# Adafruit_DAC7578P_Breakout.net
KiCad netlist of a schematic drawn in EAGLE
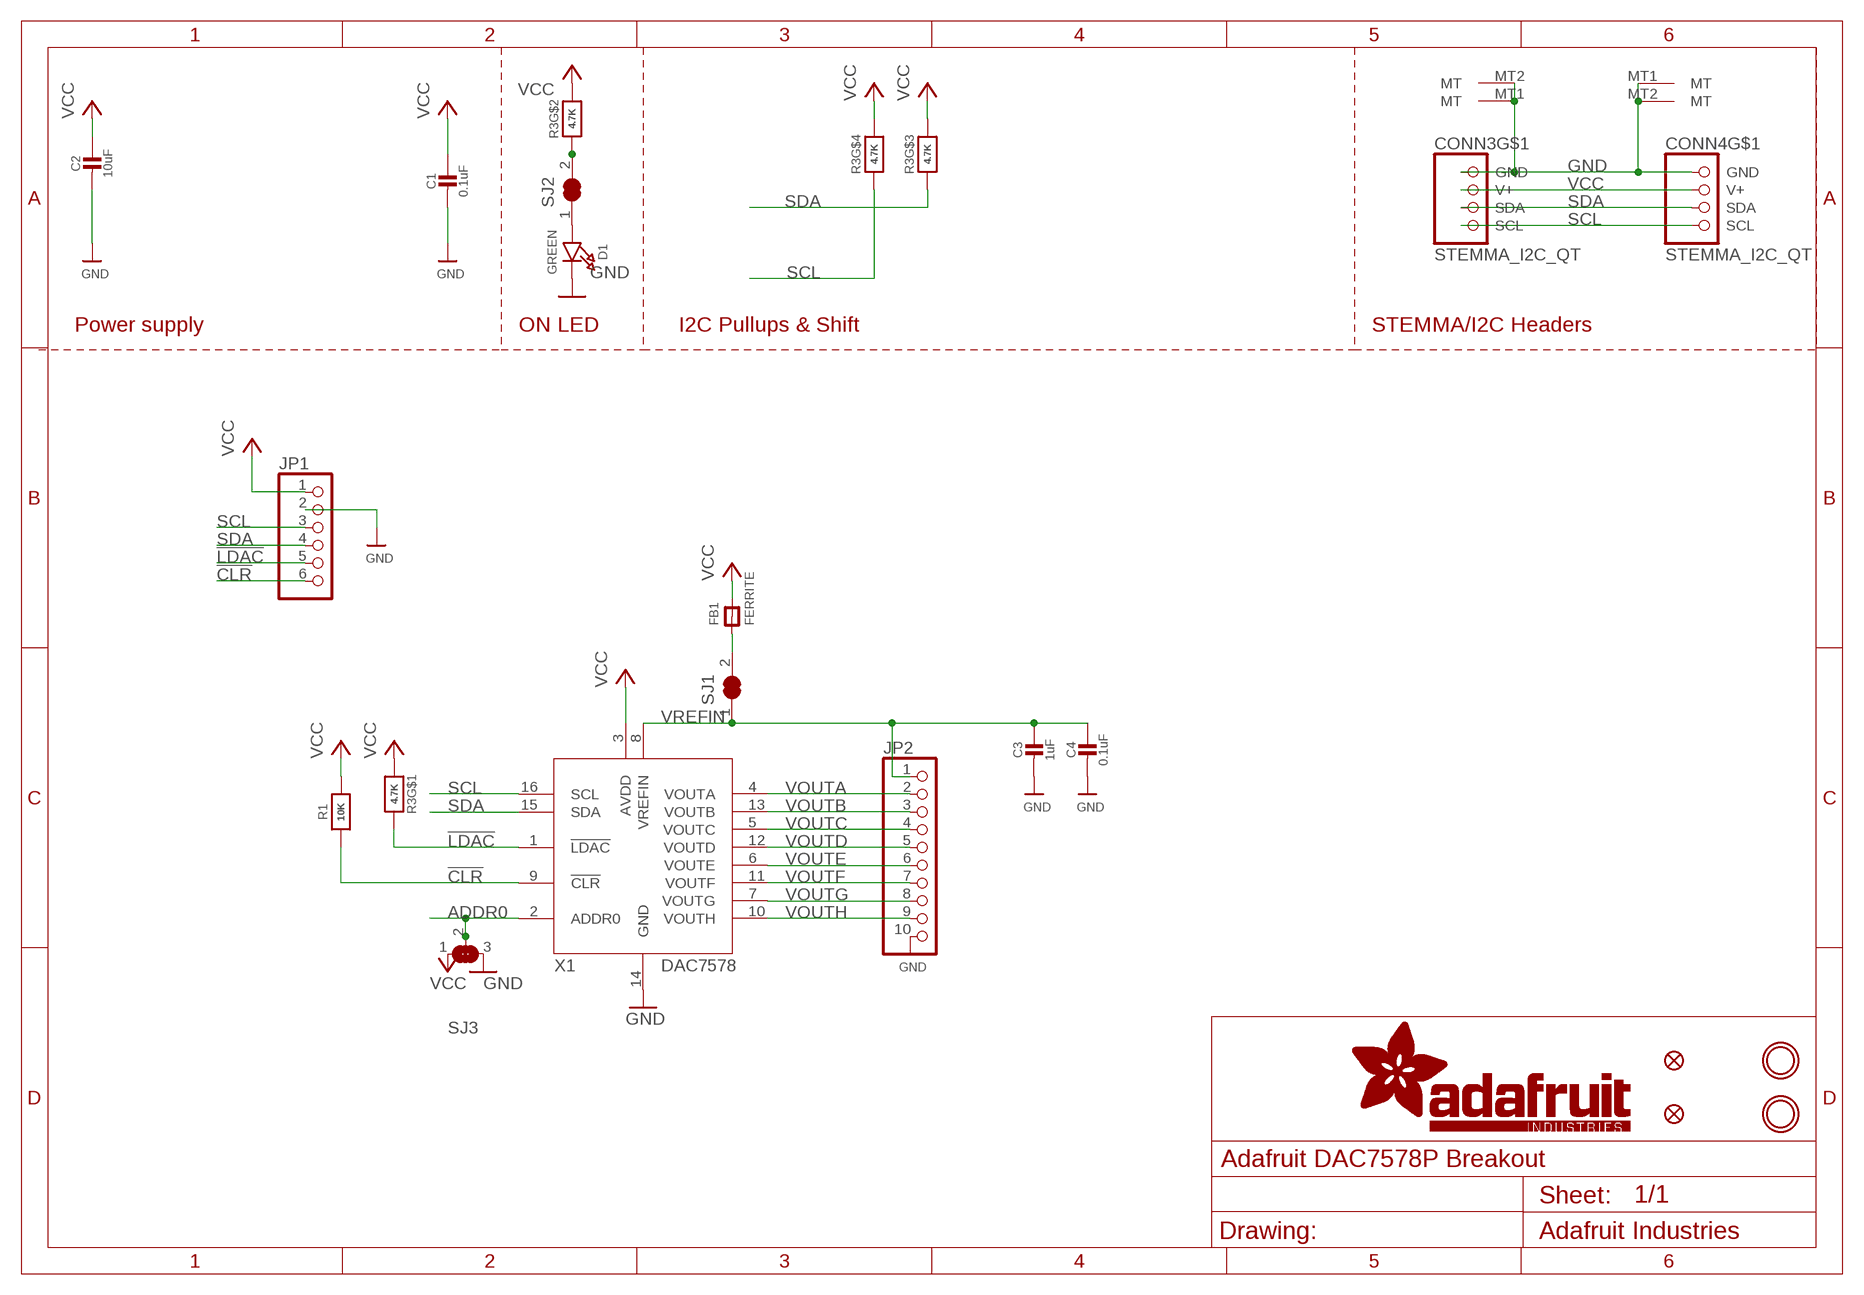
[diagram p0: schematic, sheet 1]

(export (version "E")
  (design (tool "Eeschema 10.0.6"))
  (components
    (comp (ref "C1")
      (value "0.1uF")
      (footprint "eagle-import:0603-NO")
      (libsource (lib "eagle-import") (part "CAP_CERAMIC0603_NO"))
    )
    (comp (ref "C2")
      (value "10uF")
      (footprint "eagle-import:0805-NO")
      (libsource (lib "eagle-import") (part "CAP_CERAMIC0805-NOOUTLINE"))
    )
    (comp (ref "C3")
      (value "1uF")
      (footprint "eagle-import:0603-NO")
      (libsource (lib "eagle-import") (part "CAP_CERAMIC0603_NO"))
    )
    (comp (ref "C4")
      (value "0.1uF")
      (footprint "eagle-import:0603-NO")
      (libsource (lib "eagle-import") (part "CAP_CERAMIC0603_NO"))
    )
    (comp (ref "CONN3")
      (value "STEMMA_I2C_QT")
      (footprint "eagle-import:JST_SH4")
      (libsource (lib "eagle-import") (part "STEMMA_I2C_QT"))
    )
    (comp (ref "CONN4")
      (value "STEMMA_I2C_QT")
      (footprint "eagle-import:JST_SH4")
      (libsource (lib "eagle-import") (part "STEMMA_I2C_QT"))
    )
    (comp (ref "D1")
      (value "GREEN")
      (footprint "eagle-import:CHIPLED_0603_NOOUTLINE")
      (libsource (lib "eagle-import") (part "LED0603_NOOUTLINE"))
    )
    (comp (ref "FB1")
      (value "FERRITE")
      (footprint "eagle-import:0603-NO")
      (libsource (lib "eagle-import") (part "FERRITE-0603NO"))
    )
    (comp (ref "FID3")
      (value "FIDUCIAL_0.5MM")
      (footprint "eagle-import:FIDUCIAL_0.5MM")
      (libsource (lib "eagle-import") (part "FIDUCIAL_0.5MM"))
    )
    (comp (ref "FID4")
      (value "FIDUCIAL_0.5MM")
      (footprint "eagle-import:FIDUCIAL_0.5MM")
      (libsource (lib "eagle-import") (part "FIDUCIAL_0.5MM"))
    )
    (comp (ref "JP1")
      (value "HEADER-1X670MIL")
      (footprint "eagle-import:1X06_ROUND_70")
      (libsource (lib "eagle-import") (part "HEADER-1X670MIL"))
    )
    (comp (ref "JP2")
      (value "HEADER-1X1070MIL")
      (footprint "eagle-import:1X10_ROUND70")
      (libsource (lib "eagle-import") (part "HEADER-1X1070MIL"))
    )
    (comp (ref "R1")
      (value "10K")
      (footprint "eagle-import:0603-NO")
      (libsource (lib "eagle-import") (part "RESISTOR_0603_NOOUT"))
    )
    (comp (ref "R3")
      (value "4.7K")
      (footprint "eagle-import:RESPACK_4X0603")
      (libsource (lib "eagle-import") (part "RESISTOR_4PACK"))
    )
    (comp (ref "SJ1")
      (value "SOLDERJUMPER_CLOSED")
      (footprint "eagle-import:SOLDERJUMPER_CLOSEDWIRE")
      (libsource (lib "eagle-import") (part "SOLDERJUMPER_CLOSED"))
    )
    (comp (ref "SJ2")
      (value "SOLDERJUMPER_CLOSED")
      (footprint "eagle-import:SOLDERJUMPER_CLOSEDWIRE")
      (libsource (lib "eagle-import") (part "SOLDERJUMPER_CLOSED"))
    )
    (comp (ref "SJ3")
      (value "SOLDERJUMPER_2WAY")
      (footprint "eagle-import:SOLDERJUMPER_2WAY_OPEN_NOPASTE")
      (libsource (lib "eagle-import") (part "SOLDERJUMPER_2WAY"))
    )
    (comp (ref "U$19")
      (value "MOUNTINGHOLE2.5")
      (footprint "eagle-import:MOUNTINGHOLE_2.5_PLATED")
      (libsource (lib "eagle-import") (part "MOUNTINGHOLE2.5"))
    )
    (comp (ref "U$21")
      (value "MOUNTINGHOLE2.5")
      (footprint "eagle-import:MOUNTINGHOLE_2.5_PLATED")
      (libsource (lib "eagle-import") (part "MOUNTINGHOLE2.5"))
    )
    (comp (ref "X1")
      (value "DAC7578PW")
      (footprint "eagle-import:TSSOP16")
      (libsource (lib "eagle-import") (part "DAC7578PW"))
    )
  )
  (nets
    (net (code "1") (name "/ADDR0") (class "Default")
      (node (ref "SJ3") (pin "2") (pinfunction "2_2") (pintype "passive"))
      (node (ref "X1") (pin "2") (pinfunction "ADDR0_2") (pintype "input"))
    )
    (net (code "2") (name "/SCL") (class "Default")
      (node (ref "CONN3") (pin "4") (pinfunction "SCL_4") (pintype "passive"))
      (node (ref "CONN4") (pin "4") (pinfunction "SCL_4") (pintype "passive"))
      (node (ref "JP1") (pin "3") (pinfunction "3_3") (pintype "passive"))
      (node (ref "R3") (pin "4") (pinfunction "1_4") (pintype "passive"))
      (node (ref "X1") (pin "16") (pinfunction "SCL_16") (pintype "bidirectional"))
    )
    (net (code "3") (name "/SDA") (class "Default")
      (node (ref "CONN3") (pin "3") (pinfunction "SDA_3") (pintype "passive"))
      (node (ref "CONN4") (pin "3") (pinfunction "SDA_3") (pintype "passive"))
      (node (ref "JP1") (pin "4") (pinfunction "4_4") (pintype "passive"))
      (node (ref "R3") (pin "3") (pinfunction "1_3") (pintype "passive"))
      (node (ref "X1") (pin "15") (pinfunction "SDA_15") (pintype "bidirectional"))
    )
    (net (code "4") (name "/VOUTA") (class "Default")
      (node (ref "JP2") (pin "2") (pinfunction "2_2") (pintype "passive"))
      (node (ref "X1") (pin "4") (pinfunction "VOUTA_4") (pintype "output"))
    )
    (net (code "5") (name "/VOUTB") (class "Default")
      (node (ref "JP2") (pin "3") (pinfunction "3_3") (pintype "passive"))
      (node (ref "X1") (pin "13") (pinfunction "VOUTB_13") (pintype "output"))
    )
    (net (code "6") (name "/VOUTC") (class "Default")
      (node (ref "JP2") (pin "4") (pinfunction "4_4") (pintype "passive"))
      (node (ref "X1") (pin "5") (pinfunction "VOUTC_5") (pintype "output"))
    )
    (net (code "7") (name "/VOUTD") (class "Default")
      (node (ref "JP2") (pin "5") (pinfunction "5_5") (pintype "passive"))
      (node (ref "X1") (pin "12") (pinfunction "VOUTD_12") (pintype "output"))
    )
    (net (code "8") (name "/VOUTE") (class "Default")
      (node (ref "JP2") (pin "6") (pinfunction "6_6") (pintype "passive"))
      (node (ref "X1") (pin "6") (pinfunction "VOUTE_6") (pintype "output"))
    )
    (net (code "9") (name "/VOUTF") (class "Default")
      (node (ref "JP2") (pin "7") (pinfunction "7_7") (pintype "passive"))
      (node (ref "X1") (pin "11") (pinfunction "VOUTF_11") (pintype "output"))
    )
    (net (code "10") (name "/VOUTG") (class "Default")
      (node (ref "JP2") (pin "8") (pinfunction "8_8") (pintype "passive"))
      (node (ref "X1") (pin "7") (pinfunction "VOUTG_7") (pintype "output"))
    )
    (net (code "11") (name "/VOUTH") (class "Default")
      (node (ref "JP2") (pin "9") (pinfunction "9_9") (pintype "passive"))
      (node (ref "X1") (pin "10") (pinfunction "VOUTH_10") (pintype "output"))
    )
    (net (code "12") (name "/VREFIN") (class "Default")
      (node (ref "C3") (pin "1") (pinfunction "1_1") (pintype "passive"))
      (node (ref "C4") (pin "1") (pinfunction "1_1") (pintype "passive"))
      (node (ref "JP2") (pin "1") (pinfunction "1_1") (pintype "passive"))
      (node (ref "SJ1") (pin "1") (pinfunction "1_1") (pintype "passive"))
      (node (ref "X1") (pin "8") (pinfunction "VREFIN_8") (pintype "power_in"))
    )
    (net (code "13") (name "/~{CLR}") (class "Default")
      (node (ref "JP1") (pin "6") (pinfunction "6_6") (pintype "passive"))
      (node (ref "R1") (pin "1") (pinfunction "1_1") (pintype "passive"))
      (node (ref "X1") (pin "9") (pinfunction "~{CLR}_9") (pintype "input"))
    )
    (net (code "14") (name "/~{LDAC}") (class "Default")
      (node (ref "JP1") (pin "5") (pinfunction "5_5") (pintype "passive"))
      (node (ref "R3") (pin "8") (pinfunction "2_8") (pintype "passive"))
      (node (ref "X1") (pin "1") (pinfunction "~{LDAC}_1") (pintype "input"))
    )
    (net (code "15") (name "GND") (class "Default")
      (node (ref "C1") (pin "2") (pinfunction "2_2") (pintype "passive"))
      (node (ref "C2") (pin "2") (pinfunction "2_2") (pintype "passive"))
      (node (ref "C3") (pin "2") (pinfunction "2_2") (pintype "passive"))
      (node (ref "C4") (pin "2") (pinfunction "2_2") (pintype "passive"))
      (node (ref "CONN3") (pin "1") (pinfunction "GND_1") (pintype "passive"))
      (node (ref "CONN3") (pin "MT1") (pinfunction "MT_MT1") (pintype "bidirectional"))
      (node (ref "CONN3") (pin "MT2") (pinfunction "MT_MT2") (pintype "bidirectional"))
      (node (ref "CONN4") (pin "1") (pinfunction "GND_1") (pintype "passive"))
      (node (ref "CONN4") (pin "MT1") (pinfunction "MT_MT1") (pintype "bidirectional"))
      (node (ref "CONN4") (pin "MT2") (pinfunction "MT_MT2") (pintype "bidirectional"))
      (node (ref "D1") (pin "C") (pinfunction "C_C") (pintype "passive"))
      (node (ref "JP1") (pin "2") (pinfunction "2_2") (pintype "passive"))
      (node (ref "JP2") (pin "10") (pinfunction "10_10") (pintype "passive"))
      (node (ref "SJ3") (pin "3") (pinfunction "3_3") (pintype "passive"))
      (node (ref "X1") (pin "14") (pinfunction "GND_14") (pintype "power_in"))
    )
    (net (code "16") (name "Net-(D1-PadA)") (class "Default")
      (node (ref "D1") (pin "A") (pinfunction "A_A") (pintype "passive"))
      (node (ref "SJ2") (pin "1") (pinfunction "1_1") (pintype "passive"))
    )
    (net (code "17") (name "Net-(FB1-P$1)") (class "Default")
      (node (ref "FB1") (pin "1") (pinfunction "P$1_1") (pintype "passive"))
      (node (ref "SJ1") (pin "2") (pinfunction "2_2") (pintype "passive"))
    )
    (net (code "18") (name "Net-(R3B-1)") (class "Default")
      (node (ref "R3") (pin "2") (pinfunction "1_2") (pintype "passive"))
      (node (ref "SJ2") (pin "2") (pinfunction "2_2") (pintype "passive"))
    )
    (net (code "19") (name "VCC") (class "Default")
      (node (ref "C1") (pin "1") (pinfunction "1_1") (pintype "passive"))
      (node (ref "C2") (pin "1") (pinfunction "1_1") (pintype "passive"))
      (node (ref "CONN3") (pin "2") (pinfunction "V+_2") (pintype "passive"))
      (node (ref "CONN4") (pin "2") (pinfunction "V+_2") (pintype "passive"))
      (node (ref "FB1") (pin "2") (pinfunction "P$2_2") (pintype "passive"))
      (node (ref "JP1") (pin "1") (pinfunction "1_1") (pintype "passive"))
      (node (ref "R1") (pin "2") (pinfunction "2_2") (pintype "passive"))
      (node (ref "R3") (pin "1") (pinfunction "1_1") (pintype "passive"))
      (node (ref "R3") (pin "5") (pinfunction "2_5") (pintype "passive"))
      (node (ref "R3") (pin "6") (pinfunction "2_6") (pintype "passive"))
      (node (ref "R3") (pin "7") (pinfunction "2_7") (pintype "passive"))
      (node (ref "SJ3") (pin "1") (pinfunction "1_1") (pintype "passive"))
      (node (ref "X1") (pin "3") (pinfunction "AVDD_3") (pintype "power_in"))
    )
  )
)
